# Tray2_ARM.net
KiCad netlist of a schematic drawn in Altium Designer
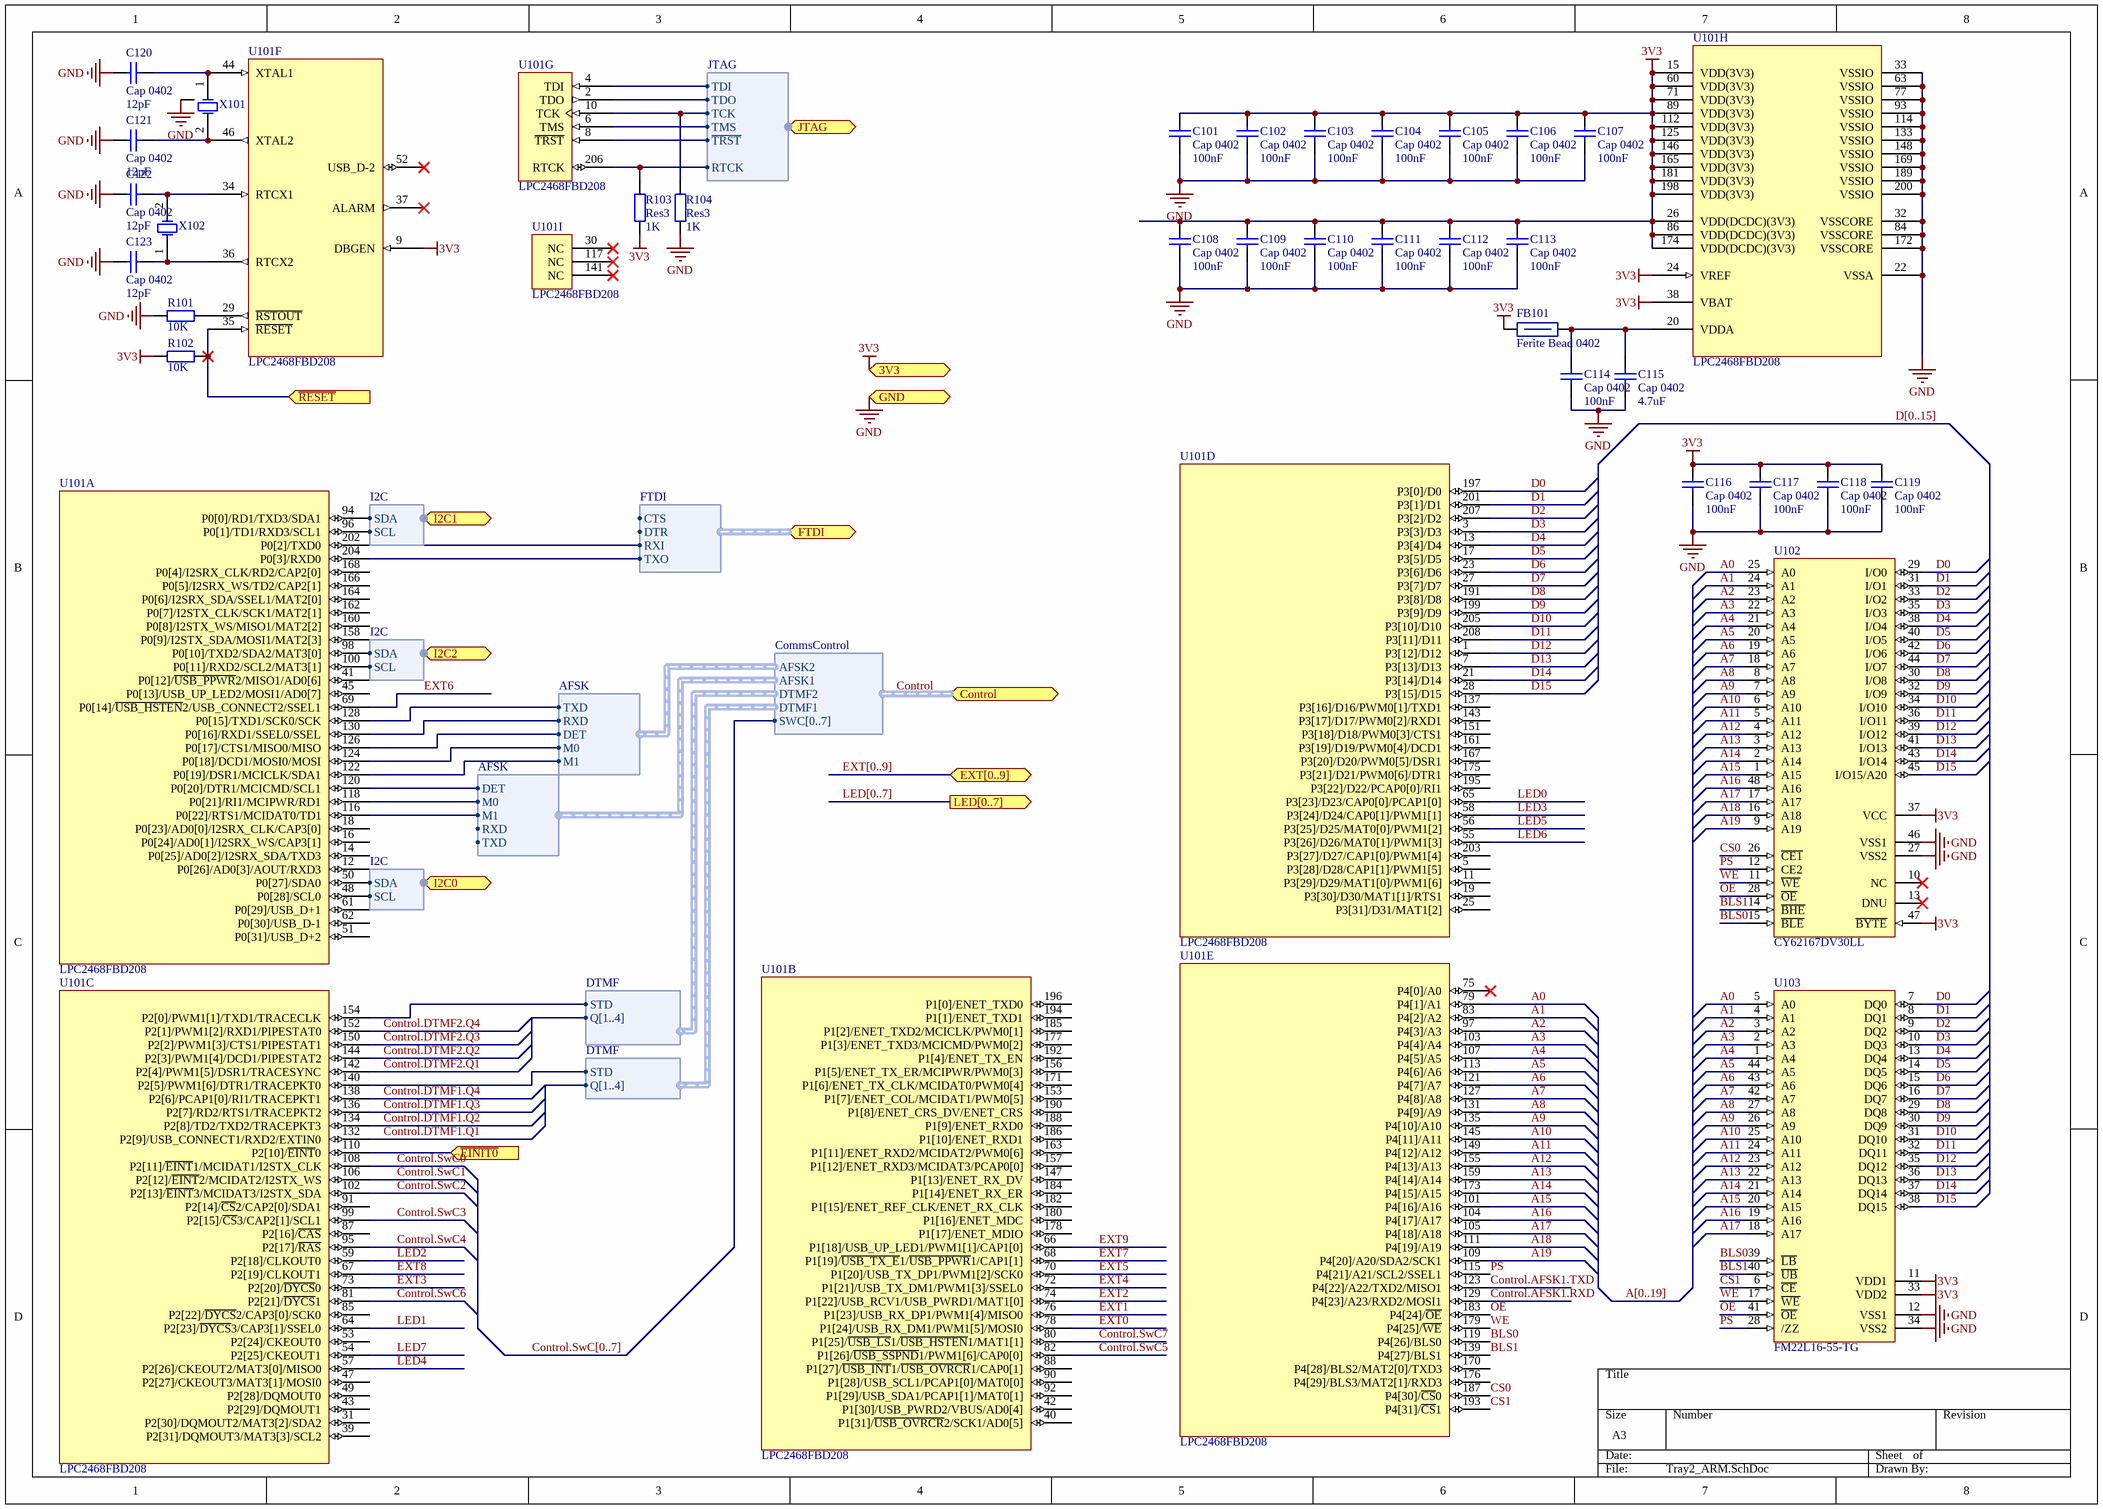
[diagram p0: Tray2_ARM.SchDoc]

(export (version "E")
  (design (tool "Eeschema 10.0.6"))
  (components
    (comp (ref "C101")
      (value "Cap 0402")
      (footprint "CAPC1005X06L")
      (description "Capacitor")
      (fields (field (name "ALTIUM_VALUE") "100nF") (field (name "PUBLISHER") "Altium Limited"))
      (libsource (lib "CSC") (part "Cap 0402"))
    )
    (comp (ref "C102")
      (value "Cap 0402")
      (footprint "CAPC1005X06L")
      (description "Capacitor")
      (fields (field (name "ALTIUM_VALUE") "100nF") (field (name "PUBLISHER") "Altium Limited"))
      (libsource (lib "CSC") (part "Cap 0402"))
    )
    (comp (ref "C103")
      (value "Cap 0402")
      (footprint "CAPC1005X06L")
      (description "Capacitor")
      (fields (field (name "ALTIUM_VALUE") "100nF") (field (name "PUBLISHER") "Altium Limited"))
      (libsource (lib "CSC") (part "Cap 0402"))
    )
    (comp (ref "C104")
      (value "Cap 0402")
      (footprint "CAPC1005X06L")
      (description "Capacitor")
      (fields (field (name "ALTIUM_VALUE") "100nF") (field (name "PUBLISHER") "Altium Limited"))
      (libsource (lib "CSC") (part "Cap 0402"))
    )
    (comp (ref "C105")
      (value "Cap 0402")
      (footprint "CAPC1005X06L")
      (description "Capacitor")
      (fields (field (name "ALTIUM_VALUE") "100nF") (field (name "PUBLISHER") "Altium Limited"))
      (libsource (lib "CSC") (part "Cap 0402"))
    )
    (comp (ref "C106")
      (value "Cap 0402")
      (footprint "CAPC1005X06L")
      (description "Capacitor")
      (fields (field (name "ALTIUM_VALUE") "100nF") (field (name "PUBLISHER") "Altium Limited"))
      (libsource (lib "CSC") (part "Cap 0402"))
    )
    (comp (ref "C107")
      (value "Cap 0402")
      (footprint "CAPC1005X06L")
      (description "Capacitor")
      (fields (field (name "ALTIUM_VALUE") "100nF") (field (name "PUBLISHER") "Altium Limited"))
      (libsource (lib "CSC") (part "Cap 0402"))
    )
    (comp (ref "C108")
      (value "Cap 0402")
      (footprint "CAPC1005X06L")
      (description "Capacitor")
      (fields (field (name "ALTIUM_VALUE") "100nF") (field (name "PUBLISHER") "Altium Limited"))
      (libsource (lib "CSC") (part "Cap 0402"))
    )
    (comp (ref "C109")
      (value "Cap 0402")
      (footprint "CAPC1005X06L")
      (description "Capacitor")
      (fields (field (name "ALTIUM_VALUE") "100nF") (field (name "PUBLISHER") "Altium Limited"))
      (libsource (lib "CSC") (part "Cap 0402"))
    )
    (comp (ref "C110")
      (value "Cap 0402")
      (footprint "CAPC1005X06L")
      (description "Capacitor")
      (fields (field (name "ALTIUM_VALUE") "100nF") (field (name "PUBLISHER") "Altium Limited"))
      (libsource (lib "CSC") (part "Cap 0402"))
    )
    (comp (ref "C111")
      (value "Cap 0402")
      (footprint "CAPC1005X06L")
      (description "Capacitor")
      (fields (field (name "ALTIUM_VALUE") "100nF") (field (name "PUBLISHER") "Altium Limited"))
      (libsource (lib "CSC") (part "Cap 0402"))
    )
    (comp (ref "C112")
      (value "Cap 0402")
      (footprint "CAPC1005X06L")
      (description "Capacitor")
      (fields (field (name "ALTIUM_VALUE") "100nF") (field (name "PUBLISHER") "Altium Limited"))
      (libsource (lib "CSC") (part "Cap 0402"))
    )
    (comp (ref "C113")
      (value "Cap 0402")
      (footprint "CAPC1005X06L")
      (description "Capacitor")
      (fields (field (name "ALTIUM_VALUE") "100nF") (field (name "PUBLISHER") "Altium Limited"))
      (libsource (lib "CSC") (part "Cap 0402"))
    )
    (comp (ref "C114")
      (value "Cap 0402")
      (footprint "CAPC1005X06L")
      (description "Capacitor")
      (fields (field (name "ALTIUM_VALUE") "100nF") (field (name "PUBLISHER") "Altium Limited"))
      (libsource (lib "CSC") (part "Cap 0402"))
    )
    (comp (ref "C115")
      (value "Cap 0402")
      (footprint "CAPC1005X06L")
      (description "Capacitor")
      (fields (field (name "ALTIUM_VALUE") "4.7uF") (field (name "PUBLISHER") "Altium Limited"))
      (libsource (lib "CSC") (part "Cap 0402"))
    )
    (comp (ref "C116")
      (value "Cap 0402")
      (footprint "CAPC1005X06L")
      (description "Capacitor")
      (fields (field (name "ALTIUM_VALUE") "100nF") (field (name "PUBLISHER") "Altium Limited"))
      (libsource (lib "CSC") (part "Cap 0402"))
    )
    (comp (ref "C117")
      (value "Cap 0402")
      (footprint "CAPC1005X06L")
      (description "Capacitor")
      (fields (field (name "ALTIUM_VALUE") "100nF") (field (name "PUBLISHER") "Altium Limited"))
      (libsource (lib "CSC") (part "Cap 0402"))
    )
    (comp (ref "C118")
      (value "Cap 0402")
      (footprint "CAPC1005X06L")
      (description "Capacitor")
      (fields (field (name "ALTIUM_VALUE") "100nF") (field (name "PUBLISHER") "Altium Limited"))
      (libsource (lib "CSC") (part "Cap 0402"))
    )
    (comp (ref "C119")
      (value "Cap 0402")
      (footprint "CAPC1005X06L")
      (description "Capacitor")
      (fields (field (name "ALTIUM_VALUE") "100nF") (field (name "PUBLISHER") "Altium Limited"))
      (libsource (lib "CSC") (part "Cap 0402"))
    )
    (comp (ref "C120")
      (value "Cap 0402")
      (footprint "CAPC1005X06L")
      (description "Capacitor")
      (fields (field (name "ALTIUM_VALUE") "12pF") (field (name "PUBLISHER") "Altium Limited"))
      (libsource (lib "CSC") (part "Cap 0402"))
    )
    (comp (ref "C121")
      (value "Cap 0402")
      (footprint "CAPC1005X06L")
      (description "Capacitor")
      (fields (field (name "ALTIUM_VALUE") "12pF") (field (name "PUBLISHER") "Altium Limited"))
      (libsource (lib "CSC") (part "Cap 0402"))
    )
    (comp (ref "C122")
      (value "Cap 0402")
      (footprint "CAPC1005X06L")
      (description "Capacitor")
      (fields (field (name "ALTIUM_VALUE") "12pF") (field (name "PUBLISHER") "Altium Limited"))
      (libsource (lib "CSC") (part "Cap 0402"))
    )
    (comp (ref "C123")
      (value "Cap 0402")
      (footprint "CAPC1005X06L")
      (description "Capacitor")
      (fields (field (name "ALTIUM_VALUE") "12pF") (field (name "PUBLISHER") "Altium Limited"))
      (libsource (lib "CSC") (part "Cap 0402"))
    )
    (comp (ref "FB101")
      (value "Ferite Bead 0402")
      (footprint "INDC1005X06L")
      (description "Ferite Bead : 0402")
      (fields (field (name "PUBLISHER") "Altium Limited"))
      (libsource (lib "CSC") (part "FB_0402"))
    )
    (comp (ref "R101")
      (value "10K")
      (footprint "RESC1005X06L")
      (description "Resistor")
      (fields (field (name "Comment") "Res3") (field (name "PUBLISHER") "Altium Limited"))
      (libsource (lib "CSC") (part "Res3"))
    )
    (comp (ref "R102")
      (value "10K")
      (footprint "RESC1005X06L")
      (description "Resistor")
      (fields (field (name "Comment") "Res3") (field (name "PUBLISHER") "Altium Limited"))
      (libsource (lib "CSC") (part "Res3"))
    )
    (comp (ref "R103")
      (value "Res3")
      (footprint "RESC1005X06L")
      (description "Resistor")
      (fields (field (name "ALTIUM_VALUE") "1K") (field (name "PUBLISHER") "Altium Limited"))
      (libsource (lib "") (part "Res3_1"))
    )
    (comp (ref "R104")
      (value "Res3")
      (footprint "RESC1005X06L")
      (description "Resistor")
      (fields (field (name "ALTIUM_VALUE") "1K") (field (name "PUBLISHER") "Altium Limited"))
      (libsource (lib "") (part "Res3_1"))
    )
    (comp (ref "U101")
      (value "LPC2468FBD208")
      (footprint "TSQFP50P3000X3000X160-208L")
      (description "ARM7 16/32-Bit Microcontroller, 512KB Flash, 98KB RAM, 208-Lead LQFP")
      (fields (field (name "PUBLISHER") "Altium Limited"))
      (libsource (lib "CSC") (part "LPC2468FBD208"))
    )
    (comp (ref "U102")
      (value "CY62167DV30LL")
      (footprint "TSSOP50P2000X120-48L")
      (description "16-Mbit (1M x 16) Static RAM")
      (fields (field (name "PUBLISHER") "Altium Limited"))
      (libsource (lib "CSC") (part "CY62167DV30LL"))
    )
    (comp (ref "U103")
      (value "FM22L16-55-TG")
      (footprint "TSOP80P1180X120-44L")
      (description "FRAM, 2MB, 3V, 60NS, 44TSOP2")
      (libsource (lib "CSC") (part "FM22L16-55-TG"))
    )
    (comp (ref "X101")
      (value "Crystal Oscilator")
      (footprint "7M")
      (description "Crystal Oscillator")
      (fields (field (name "PUBLISHER") "Altium Limited"))
      (libsource (lib "CSC") (part "C.O. 4pins"))
    )
    (comp (ref "X102")
      (value "Crystal Oscilator")
      (footprint "9H T10")
      (description "Crystal Oscillator")
      (fields (field (name "PUBLISHER") "Altium Limited"))
      (libsource (lib "CSC") (part "C.O. 2pins"))
    )
  )
  (nets
    (net (code "7") (name "/A0") (class "Default")
      (node (ref "U101") (pin "79") (pinfunction "P4[1]/A1_79") (pintype "bidirectional"))
      (node (ref "U102") (pin "25") (pinfunction "A0_25") (pintype "input"))
      (node (ref "U103") (pin "5") (pinfunction "A0_5") (pintype "input"))
    )
    (net (code "8") (name "/A1") (class "Default")
      (node (ref "U101") (pin "83") (pinfunction "P4[2]/A2_83") (pintype "bidirectional"))
      (node (ref "U102") (pin "24") (pinfunction "A1_24") (pintype "input"))
      (node (ref "U103") (pin "4") (pinfunction "A1_4") (pintype "input"))
    )
    (net (code "9") (name "/A2") (class "Default")
      (node (ref "U101") (pin "97") (pinfunction "P4[3]/A3_97") (pintype "bidirectional"))
      (node (ref "U102") (pin "23") (pinfunction "A2_23") (pintype "input"))
      (node (ref "U103") (pin "3") (pinfunction "A2_3") (pintype "input"))
    )
    (net (code "10") (name "/A3") (class "Default")
      (node (ref "U101") (pin "103") (pinfunction "P4[4]/A4_103") (pintype "bidirectional"))
      (node (ref "U102") (pin "22") (pinfunction "A3_22") (pintype "input"))
      (node (ref "U103") (pin "2") (pinfunction "A3_2") (pintype "input"))
    )
    (net (code "11") (name "/A4") (class "Default")
      (node (ref "U101") (pin "107") (pinfunction "P4[5]/A5_107") (pintype "bidirectional"))
      (node (ref "U102") (pin "21") (pinfunction "A4_21") (pintype "input"))
      (node (ref "U103") (pin "1") (pinfunction "A4_1") (pintype "input"))
    )
    (net (code "12") (name "/A5") (class "Default")
      (node (ref "U101") (pin "113") (pinfunction "P4[6]/A6_113") (pintype "bidirectional"))
      (node (ref "U102") (pin "20") (pinfunction "A5_20") (pintype "input"))
      (node (ref "U103") (pin "44") (pinfunction "A5_44") (pintype "input"))
    )
    (net (code "13") (name "/A6") (class "Default")
      (node (ref "U101") (pin "121") (pinfunction "P4[7]/A7_121") (pintype "bidirectional"))
      (node (ref "U102") (pin "19") (pinfunction "A6_19") (pintype "input"))
      (node (ref "U103") (pin "43") (pinfunction "A6_43") (pintype "input"))
    )
    (net (code "14") (name "/A7") (class "Default")
      (node (ref "U101") (pin "127") (pinfunction "P4[8]/A8_127") (pintype "bidirectional"))
      (node (ref "U102") (pin "18") (pinfunction "A7_18") (pintype "input"))
      (node (ref "U103") (pin "42") (pinfunction "A7_42") (pintype "input"))
    )
    (net (code "15") (name "/A8") (class "Default")
      (node (ref "U101") (pin "131") (pinfunction "P4[9]/A9_131") (pintype "bidirectional"))
      (node (ref "U102") (pin "8") (pinfunction "A8_8") (pintype "input"))
      (node (ref "U103") (pin "27") (pinfunction "A8_27") (pintype "input"))
    )
    (net (code "16") (name "/A9") (class "Default")
      (node (ref "U101") (pin "135") (pinfunction "P4[10]/A10_135") (pintype "bidirectional"))
      (node (ref "U102") (pin "7") (pinfunction "A9_7") (pintype "input"))
      (node (ref "U103") (pin "26") (pinfunction "A9_26") (pintype "input"))
    )
    (net (code "17") (name "/A10") (class "Default")
      (node (ref "U101") (pin "145") (pinfunction "P4[11]/A11_145") (pintype "bidirectional"))
      (node (ref "U102") (pin "6") (pinfunction "A10_6") (pintype "input"))
      (node (ref "U103") (pin "25") (pinfunction "A10_25") (pintype "input"))
    )
    (net (code "18") (name "/A11") (class "Default")
      (node (ref "U101") (pin "149") (pinfunction "P4[12]/A12_149") (pintype "bidirectional"))
      (node (ref "U102") (pin "5") (pinfunction "A11_5") (pintype "input"))
      (node (ref "U103") (pin "24") (pinfunction "A11_24") (pintype "input"))
    )
    (net (code "19") (name "/A12") (class "Default")
      (node (ref "U101") (pin "155") (pinfunction "P4[13]/A13_155") (pintype "bidirectional"))
      (node (ref "U102") (pin "4") (pinfunction "A12_4") (pintype "input"))
      (node (ref "U103") (pin "23") (pinfunction "A12_23") (pintype "input"))
    )
    (net (code "20") (name "/A13") (class "Default")
      (node (ref "U101") (pin "159") (pinfunction "P4[14]/A14_159") (pintype "bidirectional"))
      (node (ref "U102") (pin "3") (pinfunction "A13_3") (pintype "input"))
      (node (ref "U103") (pin "22") (pinfunction "A13_22") (pintype "input"))
    )
    (net (code "21") (name "/A14") (class "Default")
      (node (ref "U101") (pin "173") (pinfunction "P4[15]/A15_173") (pintype "bidirectional"))
      (node (ref "U102") (pin "2") (pinfunction "A14_2") (pintype "input"))
      (node (ref "U103") (pin "21") (pinfunction "A14_21") (pintype "input"))
    )
    (net (code "22") (name "/A15") (class "Default")
      (node (ref "U101") (pin "101") (pinfunction "P4[16]/A16_101") (pintype "bidirectional"))
      (node (ref "U102") (pin "1") (pinfunction "A15_1") (pintype "input"))
      (node (ref "U103") (pin "20") (pinfunction "A15_20") (pintype "input"))
    )
    (net (code "23") (name "/A16") (class "Default")
      (node (ref "U101") (pin "104") (pinfunction "P4[17]/A17_104") (pintype "bidirectional"))
      (node (ref "U102") (pin "48") (pinfunction "A16_48") (pintype "input"))
      (node (ref "U103") (pin "19") (pinfunction "A16_19") (pintype "input"))
    )
    (net (code "24") (name "/A17") (class "Default")
      (node (ref "U101") (pin "105") (pinfunction "P4[18]/A18_105") (pintype "bidirectional"))
      (node (ref "U102") (pin "17") (pinfunction "A17_17") (pintype "input"))
      (node (ref "U103") (pin "18") (pinfunction "A17_18") (pintype "input"))
    )
    (net (code "25") (name "/A18") (class "Default")
      (node (ref "U101") (pin "111") (pinfunction "P4[19]/A19_111") (pintype "bidirectional"))
      (node (ref "U102") (pin "16") (pinfunction "A18_16") (pintype "input"))
    )
    (net (code "26") (name "/A19") (class "Default")
      (node (ref "U101") (pin "109") (pinfunction "P4[20]/A20/SDA2/SCK1_109") (pintype "bidirectional"))
      (node (ref "U102") (pin "9") (pinfunction "A19_9") (pintype "input"))
    )
    (net (code "28") (name "/BLS0") (class "Default")
      (node (ref "U101") (pin "119") (pinfunction "P4[26]/BLS0_119") (pintype "bidirectional"))
      (node (ref "U102") (pin "15") (pinfunction "~{BLE}_15") (pintype "input"))
      (node (ref "U103") (pin "39") (pinfunction "~{LB}_39") (pintype "input"))
    )
    (net (code "29") (name "/BLS1") (class "Default")
      (node (ref "U101") (pin "139") (pinfunction "P4[27]/BLS1_139") (pintype "bidirectional"))
      (node (ref "U102") (pin "14") (pinfunction "~{BHE}_14") (pintype "input"))
      (node (ref "U103") (pin "40") (pinfunction "~{UB}_40") (pintype "input"))
    )
    (net (code "30") (name "/CS0") (class "Default")
      (node (ref "U101") (pin "187") (pinfunction "P4[30]/~{CS}0_187") (pintype "bidirectional"))
      (node (ref "U102") (pin "26") (pinfunction "~{CE1}_26") (pintype "input"))
    )
    (net (code "31") (name "/CS1") (class "Default")
      (node (ref "U101") (pin "193") (pinfunction "P4[31]/~{CS}1_193") (pintype "bidirectional"))
      (node (ref "U103") (pin "6") (pinfunction "~{CE}_6") (pintype "input"))
    )
    (net (code "32") (name "/Control.AFSK1.RXD") (class "Default")
      (node (ref "U101") (pin "129") (pinfunction "P4[23]/A23/RXD2/MOSI1_129") (pintype "bidirectional"))
    )
    (net (code "33") (name "/Control.AFSK1.TXD") (class "Default")
      (node (ref "U101") (pin "123") (pinfunction "P4[22]/A22/TXD2/MISO1_123") (pintype "bidirectional"))
    )
    (net (code "34") (name "/Control.DTMF1.Q1") (class "Default")
      (node (ref "U101") (pin "132") (pinfunction "P2[9]/USB_CONNECT1/RXD2/EXTIN0_132") (pintype "bidirectional"))
    )
    (net (code "35") (name "/Control.DTMF1.Q2") (class "Default")
      (node (ref "U101") (pin "134") (pinfunction "P2[8]/TD2/TXD2/TRACEPKT3_134") (pintype "bidirectional"))
    )
    (net (code "36") (name "/Control.DTMF1.Q3") (class "Default")
      (node (ref "U101") (pin "136") (pinfunction "P2[7]/RD2/RTS1/TRACEPKT2_136") (pintype "bidirectional"))
    )
    (net (code "37") (name "/Control.DTMF1.Q4") (class "Default")
      (node (ref "U101") (pin "138") (pinfunction "P2[6]/PCAP1[0]/RI1/TRACEPKT1_138") (pintype "bidirectional"))
    )
    (net (code "38") (name "/Control.DTMF2.Q1") (class "Default")
      (node (ref "U101") (pin "142") (pinfunction "P2[4]/PWM1[5]/DSR1/TRACESYNC_142") (pintype "bidirectional"))
    )
    (net (code "39") (name "/Control.DTMF2.Q2") (class "Default")
      (node (ref "U101") (pin "144") (pinfunction "P2[3]/PWM1[4]/DCD1/PIPESTAT2_144") (pintype "bidirectional"))
    )
    (net (code "40") (name "/Control.DTMF2.Q3") (class "Default")
      (node (ref "U101") (pin "150") (pinfunction "P2[2]/PWM1[3]/CTS1/PIPESTAT1_150") (pintype "bidirectional"))
    )
    (net (code "41") (name "/Control.DTMF2.Q4") (class "Default")
      (node (ref "U101") (pin "152") (pinfunction "P2[1]/PWM1[2]/RXD1/PIPESTAT0_152") (pintype "bidirectional"))
    )
    (net (code "42") (name "/Control.SwC0") (class "Default")
      (node (ref "U101") (pin "108") (pinfunction "P2[11]/~{EINT}1/MCIDAT1/I2STX_CLK_108") (pintype "bidirectional"))
    )
    (net (code "43") (name "/Control.SwC1") (class "Default")
      (node (ref "U101") (pin "106") (pinfunction "P2[12]/~{EINT}2/MCIDAT2/I2STX_WS_106") (pintype "bidirectional"))
    )
    (net (code "44") (name "/Control.SwC2") (class "Default")
      (node (ref "U101") (pin "102") (pinfunction "P2[13]/~{EINT}3/MCIDAT3/I2STX_SDA_102") (pintype "bidirectional"))
    )
    (net (code "45") (name "/Control.SwC3") (class "Default")
      (node (ref "U101") (pin "99") (pinfunction "P2[15]/~{CS}3/CAP2[1]/SCL1_99") (pintype "bidirectional"))
    )
    (net (code "46") (name "/Control.SwC4") (class "Default")
      (node (ref "U101") (pin "95") (pinfunction "P2[17]/~{RAS}_95") (pintype "bidirectional"))
    )
    (net (code "47") (name "/Control.SwC5") (class "Default")
      (node (ref "U101") (pin "82") (pinfunction "P1[26]/~{USB_SSPND}1/PWM1[6]/CAP0[0]_82") (pintype "bidirectional"))
    )
    (net (code "48") (name "/Control.SwC6") (class "Default")
      (node (ref "U101") (pin "81") (pinfunction "P2[21]/~{DYCS}1_81") (pintype "bidirectional"))
    )
    (net (code "49") (name "/Control.SwC7") (class "Default")
      (node (ref "U101") (pin "80") (pinfunction "P1[25]/~{USB_LS}1/~{USB_HSTEN}1/MAT1[1]_80") (pintype "bidirectional"))
    )
    (net (code "50") (name "/D0") (class "Default")
      (node (ref "U101") (pin "197") (pinfunction "P3[0]/D0_197") (pintype "bidirectional"))
      (node (ref "U102") (pin "29") (pinfunction "I/O0_29") (pintype "bidirectional"))
      (node (ref "U103") (pin "7") (pinfunction "DQ0_7") (pintype "bidirectional"))
    )
    (net (code "51") (name "/D1") (class "Default")
      (node (ref "U101") (pin "201") (pinfunction "P3[1]/D1_201") (pintype "bidirectional"))
      (node (ref "U102") (pin "31") (pinfunction "I/O1_31") (pintype "bidirectional"))
      (node (ref "U103") (pin "8") (pinfunction "DQ1_8") (pintype "bidirectional"))
    )
    (net (code "52") (name "/D2") (class "Default")
      (node (ref "U101") (pin "207") (pinfunction "P3[2]/D2_207") (pintype "bidirectional"))
      (node (ref "U102") (pin "33") (pinfunction "I/O2_33") (pintype "bidirectional"))
      (node (ref "U103") (pin "9") (pinfunction "DQ2_9") (pintype "bidirectional"))
    )
    (net (code "53") (name "/D3") (class "Default")
      (node (ref "U101") (pin "3") (pinfunction "P3[3]/D3_3") (pintype "bidirectional"))
      (node (ref "U102") (pin "35") (pinfunction "I/O3_35") (pintype "bidirectional"))
      (node (ref "U103") (pin "10") (pinfunction "DQ3_10") (pintype "bidirectional"))
    )
    (net (code "54") (name "/D4") (class "Default")
      (node (ref "U101") (pin "13") (pinfunction "P3[4]/D4_13") (pintype "bidirectional"))
      (node (ref "U102") (pin "38") (pinfunction "I/O4_38") (pintype "bidirectional"))
      (node (ref "U103") (pin "13") (pinfunction "DQ4_13") (pintype "bidirectional"))
    )
    (net (code "55") (name "/D5") (class "Default")
      (node (ref "U101") (pin "17") (pinfunction "P3[5]/D5_17") (pintype "bidirectional"))
      (node (ref "U102") (pin "40") (pinfunction "I/O5_40") (pintype "bidirectional"))
      (node (ref "U103") (pin "14") (pinfunction "DQ5_14") (pintype "bidirectional"))
    )
    (net (code "56") (name "/D6") (class "Default")
      (node (ref "U101") (pin "23") (pinfunction "P3[6]/D6_23") (pintype "bidirectional"))
      (node (ref "U102") (pin "42") (pinfunction "I/O6_42") (pintype "bidirectional"))
      (node (ref "U103") (pin "15") (pinfunction "DQ6_15") (pintype "bidirectional"))
    )
    (net (code "57") (name "/D7") (class "Default")
      (node (ref "U101") (pin "27") (pinfunction "P3[7]/D7_27") (pintype "bidirectional"))
      (node (ref "U102") (pin "44") (pinfunction "I/O7_44") (pintype "bidirectional"))
      (node (ref "U103") (pin "16") (pinfunction "DQ7_16") (pintype "bidirectional"))
    )
    (net (code "58") (name "/D8") (class "Default")
      (node (ref "U101") (pin "191") (pinfunction "P3[8]/D8_191") (pintype "bidirectional"))
      (node (ref "U102") (pin "30") (pinfunction "I/O8_30") (pintype "bidirectional"))
      (node (ref "U103") (pin "29") (pinfunction "DQ8_29") (pintype "bidirectional"))
    )
    (net (code "59") (name "/D9") (class "Default")
      (node (ref "U101") (pin "199") (pinfunction "P3[9]/D9_199") (pintype "bidirectional"))
      (node (ref "U102") (pin "32") (pinfunction "I/O9_32") (pintype "bidirectional"))
      (node (ref "U103") (pin "30") (pinfunction "DQ9_30") (pintype "bidirectional"))
    )
    (net (code "60") (name "/D10") (class "Default")
      (node (ref "U101") (pin "205") (pinfunction "P3[10]/D10_205") (pintype "bidirectional"))
      (node (ref "U102") (pin "34") (pinfunction "I/O10_34") (pintype "bidirectional"))
      (node (ref "U103") (pin "31") (pinfunction "DQ10_31") (pintype "bidirectional"))
    )
    (net (code "61") (name "/D11") (class "Default")
      (node (ref "U101") (pin "208") (pinfunction "P3[11]/D11_208") (pintype "bidirectional"))
      (node (ref "U102") (pin "36") (pinfunction "I/O11_36") (pintype "bidirectional"))
      (node (ref "U103") (pin "32") (pinfunction "DQ11_32") (pintype "bidirectional"))
    )
    (net (code "62") (name "/D12") (class "Default")
      (node (ref "U101") (pin "1") (pinfunction "P3[12]/D12_1") (pintype "bidirectional"))
      (node (ref "U102") (pin "39") (pinfunction "I/O12_39") (pintype "bidirectional"))
      (node (ref "U103") (pin "35") (pinfunction "DQ12_35") (pintype "bidirectional"))
    )
    (net (code "63") (name "/D13") (class "Default")
      (node (ref "U101") (pin "7") (pinfunction "P3[13]/D13_7") (pintype "bidirectional"))
      (node (ref "U102") (pin "41") (pinfunction "I/O13_41") (pintype "bidirectional"))
      (node (ref "U103") (pin "36") (pinfunction "DQ13_36") (pintype "bidirectional"))
    )
    (net (code "64") (name "/D14") (class "Default")
      (node (ref "U101") (pin "21") (pinfunction "P3[14]/D14_21") (pintype "bidirectional"))
      (node (ref "U102") (pin "43") (pinfunction "I/O14_43") (pintype "bidirectional"))
      (node (ref "U103") (pin "37") (pinfunction "DQ14_37") (pintype "bidirectional"))
    )
    (net (code "65") (name "/D15") (class "Default")
      (node (ref "U101") (pin "28") (pinfunction "P3[15]/D15_28") (pintype "bidirectional"))
      (node (ref "U102") (pin "45") (pinfunction "I/O15/A20_45") (pintype "bidirectional"))
      (node (ref "U103") (pin "38") (pinfunction "DQ15_38") (pintype "bidirectional"))
    )
    (net (code "68") (name "/EXT0") (class "Default")
      (node (ref "U101") (pin "78") (pinfunction "P1[24]/USB_RX_DM1/PWM1[5]/MOSI0_78") (pintype "bidirectional"))
    )
    (net (code "69") (name "/EXT1") (class "Default")
      (node (ref "U101") (pin "76") (pinfunction "P1[23]/USB_RX_DP1/PWM1[4]/MISO0_76") (pintype "bidirectional"))
    )
    (net (code "70") (name "/EXT2") (class "Default")
      (node (ref "U101") (pin "74") (pinfunction "P1[22]/USB_RCV1/USB_PWRD1/MAT1[0]_74") (pintype "bidirectional"))
    )
    (net (code "71") (name "/EXT3") (class "Default")
      (node (ref "U101") (pin "73") (pinfunction "P2[20]/~{DYCS}0_73") (pintype "bidirectional"))
    )
    (net (code "72") (name "/EXT4") (class "Default")
      (node (ref "U101") (pin "72") (pinfunction "P1[21]/USB_TX_DM1/PWM1[3]/SSEL0_72") (pintype "bidirectional"))
    )
    (net (code "73") (name "/EXT5") (class "Default")
      (node (ref "U101") (pin "70") (pinfunction "P1[20]/USB_TX_DP1/PWM1[2]/SCK0_70") (pintype "bidirectional"))
    )
    (net (code "74") (name "/EXT6") (class "Default")
      (node (ref "U101") (pin "69") (pinfunction "P0[14]/~{USB_HSTEN}2/USB_CONNECT2/SSEL1_69") (pintype "bidirectional"))
    )
    (net (code "75") (name "/EXT7") (class "Default")
      (node (ref "U101") (pin "68") (pinfunction "P1[19]/~{USB_TX_E}1/~{USB_PPWR}1/CAP1[1]_68") (pintype "bidirectional"))
    )
    (net (code "76") (name "/EXT8") (class "Default")
      (node (ref "U101") (pin "67") (pinfunction "P2[19]/CLKOUT1_67") (pintype "bidirectional"))
    )
    (net (code "77") (name "/EXT9") (class "Default")
      (node (ref "U101") (pin "66") (pinfunction "P1[18]/USB_UP_LED1/PWM1[1]/CAP1[0]_66") (pintype "bidirectional"))
    )
    (net (code "79") (name "/LED0") (class "Default")
      (node (ref "U101") (pin "65") (pinfunction "P3[23]/D23/CAP0[0]/PCAP1[0]_65") (pintype "bidirectional"))
    )
    (net (code "80") (name "/LED1") (class "Default")
      (node (ref "U101") (pin "64") (pinfunction "P2[23]/~{DYCS}3/CAP3[1]/SSEL0_64") (pintype "bidirectional"))
    )
    (net (code "81") (name "/LED2") (class "Default")
      (node (ref "U101") (pin "59") (pinfunction "P2[18]/CLKOUT0_59") (pintype "bidirectional"))
    )
    (net (code "82") (name "/LED3") (class "Default")
      (node (ref "U101") (pin "58") (pinfunction "P3[24]/D24/CAP0[1]/PWM1[1]_58") (pintype "bidirectional"))
    )
    (net (code "83") (name "/LED4") (class "Default")
      (node (ref "U101") (pin "57") (pinfunction "P2[26]/CKEOUT2/MAT3[0]/MISO0_57") (pintype "bidirectional"))
    )
    (net (code "84") (name "/LED5") (class "Default")
      (node (ref "U101") (pin "56") (pinfunction "P3[25]/D25/MAT0[0]/PWM1[2]_56") (pintype "bidirectional"))
    )
    (net (code "85") (name "/LED6") (class "Default")
      (node (ref "U101") (pin "55") (pinfunction "P3[26]/D26/MAT0[1]/PWM1[3]_55") (pintype "bidirectional"))
    )
    (net (code "86") (name "/LED7") (class "Default")
      (node (ref "U101") (pin "54") (pinfunction "P2[25]/CKEOUT1_54") (pintype "bidirectional"))
    )
    (net (code "88") (name "/OE") (class "Default")
      (node (ref "U101") (pin "183") (pinfunction "P4[24]/~{OE}_183") (pintype "bidirectional"))
      (node (ref "U102") (pin "28") (pinfunction "~{OE}_28") (pintype "input"))
      (node (ref "U103") (pin "41") (pinfunction "~{OE}_41") (pintype "input"))
    )
    (net (code "89") (name "/PS") (class "Default")
      (node (ref "U101") (pin "115") (pinfunction "P4[21]/A21/SCL2/SSEL1_115") (pintype "bidirectional"))
      (node (ref "U102") (pin "12") (pinfunction "CE2_12") (pintype "input"))
      (node (ref "U103") (pin "28") (pinfunction "/ZZ_28") (pintype "input"))
    )
    (net (code "90") (name "/RTCK") (class "Default")
      (node (ref "R103") (pin "1") (pinfunction "1_1") (pintype "passive"))
      (node (ref "U101") (pin "206") (pinfunction "RTCK_206") (pintype "bidirectional"))
    )
    (net (code "91") (name "/RXI") (class "Default")
      (node (ref "U101") (pin "202") (pinfunction "P0[2]/TXD0_202") (pintype "bidirectional"))
    )
    (net (code "92") (name "/TCK") (class "Default")
      (node (ref "R104") (pin "1") (pinfunction "1_1") (pintype "passive"))
      (node (ref "U101") (pin "10") (pinfunction "TCK_10") (pintype "input"))
    )
    (net (code "93") (name "/TDI") (class "Default")
      (node (ref "U101") (pin "4") (pinfunction "TDI_4") (pintype "input"))
    )
    (net (code "94") (name "/TDO") (class "Default")
      (node (ref "U101") (pin "2") (pinfunction "TDO_2") (pintype "output"))
    )
    (net (code "95") (name "/TMS") (class "Default")
      (node (ref "U101") (pin "6") (pinfunction "TMS_6") (pintype "input"))
    )
    (net (code "96") (name "/TXO") (class "Default")
      (node (ref "U101") (pin "204") (pinfunction "P0[3]/RXD0_204") (pintype "bidirectional"))
    )
    (net (code "97") (name "/WE") (class "Default")
      (node (ref "U101") (pin "179") (pinfunction "P4[25]/~{WE}_179") (pintype "bidirectional"))
      (node (ref "U102") (pin "11") (pinfunction "~{WE}_11") (pintype "input"))
      (node (ref "U103") (pin "17") (pinfunction "~{WE}_17") (pintype "input"))
    )
    (net (code "104") (name "/~{EINIT0}") (class "Default")
      (node (ref "U101") (pin "110") (pinfunction "P2[10]/~{EINT}0_110") (pintype "bidirectional"))
    )
    (net (code "105") (name "/~{RESET}") (class "Default")
      (node (ref "R102") (pin "1") (pinfunction "1_1") (pintype "passive"))
      (node (ref "U101") (pin "35") (pinfunction "~{RESET}_35") (pintype "input"))
    )
    (net (code "106") (name "/~{TRST}") (class "Default")
      (node (ref "U101") (pin "8") (pinfunction "~{TRST}_8") (pintype "input"))
    )
    (net (code "107") (name "3V3") (class "Default")
      (node (ref "C101") (pin "2") (pinfunction "2_2") (pintype "passive"))
      (node (ref "C102") (pin "2") (pinfunction "2_2") (pintype "passive"))
      (node (ref "C103") (pin "2") (pinfunction "2_2") (pintype "passive"))
      (node (ref "C104") (pin "2") (pinfunction "2_2") (pintype "passive"))
      (node (ref "C105") (pin "2") (pinfunction "2_2") (pintype "passive"))
      (node (ref "C106") (pin "2") (pinfunction "2_2") (pintype "passive"))
      (node (ref "C107") (pin "2") (pinfunction "2_2") (pintype "passive"))
      (node (ref "C108") (pin "2") (pinfunction "2_2") (pintype "passive"))
      (node (ref "C109") (pin "2") (pinfunction "2_2") (pintype "passive"))
      (node (ref "C110") (pin "2") (pinfunction "2_2") (pintype "passive"))
      (node (ref "C111") (pin "2") (pinfunction "2_2") (pintype "passive"))
      (node (ref "C112") (pin "2") (pinfunction "2_2") (pintype "passive"))
      (node (ref "C113") (pin "2") (pinfunction "2_2") (pintype "passive"))
      (node (ref "C116") (pin "2") (pinfunction "2_2") (pintype "passive"))
      (node (ref "C117") (pin "2") (pinfunction "2_2") (pintype "passive"))
      (node (ref "C118") (pin "2") (pinfunction "2_2") (pintype "passive"))
      (node (ref "C119") (pin "2") (pinfunction "2_2") (pintype "passive"))
      (node (ref "FB101") (pin "1") (pinfunction "1_1") (pintype "passive"))
      (node (ref "R102") (pin "2") (pinfunction "2_2") (pintype "passive"))
      (node (ref "R103") (pin "2") (pinfunction "2_2") (pintype "passive"))
      (node (ref "U101") (pin "112") (pinfunction "VDD(3V3)_112") (pintype "power_in"))
      (node (ref "U101") (pin "125") (pinfunction "VDD(3V3)_125") (pintype "power_in"))
      (node (ref "U101") (pin "146") (pinfunction "VDD(3V3)_146") (pintype "power_in"))
      (node (ref "U101") (pin "15") (pinfunction "VDD(3V3)_15") (pintype "power_in"))
      (node (ref "U101") (pin "165") (pinfunction "VDD(3V3)_165") (pintype "power_in"))
      (node (ref "U101") (pin "174") (pinfunction "VDD(DCDC)(3V3)_174") (pintype "power_in"))
      (node (ref "U101") (pin "181") (pinfunction "VDD(3V3)_181") (pintype "power_in"))
      (node (ref "U101") (pin "198") (pinfunction "VDD(3V3)_198") (pintype "power_in"))
      (node (ref "U101") (pin "24") (pinfunction "VREF_24") (pintype "input"))
      (node (ref "U101") (pin "26") (pinfunction "VDD(DCDC)(3V3)_26") (pintype "power_in"))
      (node (ref "U101") (pin "38") (pinfunction "VBAT_38") (pintype "power_in"))
      (node (ref "U101") (pin "60") (pinfunction "VDD(3V3)_60") (pintype "power_in"))
      (node (ref "U101") (pin "71") (pinfunction "VDD(3V3)_71") (pintype "power_in"))
      (node (ref "U101") (pin "86") (pinfunction "VDD(DCDC)(3V3)_86") (pintype "power_in"))
      (node (ref "U101") (pin "89") (pinfunction "VDD(3V3)_89") (pintype "power_in"))
      (node (ref "U101") (pin "9") (pinfunction "DBGEN_9") (pintype "input"))
      (node (ref "U102") (pin "37") (pinfunction "VCC_37") (pintype "power_in"))
      (node (ref "U102") (pin "47") (pinfunction "~{BYTE}_47") (pintype "input"))
      (node (ref "U103") (pin "11") (pinfunction "VDD1_11") (pintype "power_in"))
      (node (ref "U103") (pin "33") (pinfunction "VDD2_33") (pintype "power_in"))
    )
    (net (code "108") (name "GND") (class "Default")
      (node (ref "C101") (pin "1") (pinfunction "1_1") (pintype "passive"))
      (node (ref "C102") (pin "1") (pinfunction "1_1") (pintype "passive"))
      (node (ref "C103") (pin "1") (pinfunction "1_1") (pintype "passive"))
      (node (ref "C104") (pin "1") (pinfunction "1_1") (pintype "passive"))
      (node (ref "C105") (pin "1") (pinfunction "1_1") (pintype "passive"))
      (node (ref "C106") (pin "1") (pinfunction "1_1") (pintype "passive"))
      (node (ref "C107") (pin "1") (pinfunction "1_1") (pintype "passive"))
      (node (ref "C108") (pin "1") (pinfunction "1_1") (pintype "passive"))
      (node (ref "C109") (pin "1") (pinfunction "1_1") (pintype "passive"))
      (node (ref "C110") (pin "1") (pinfunction "1_1") (pintype "passive"))
      (node (ref "C111") (pin "1") (pinfunction "1_1") (pintype "passive"))
      (node (ref "C112") (pin "1") (pinfunction "1_1") (pintype "passive"))
      (node (ref "C113") (pin "1") (pinfunction "1_1") (pintype "passive"))
      (node (ref "C114") (pin "1") (pinfunction "1_1") (pintype "passive"))
      (node (ref "C115") (pin "1") (pinfunction "1_1") (pintype "passive"))
      (node (ref "C116") (pin "1") (pinfunction "1_1") (pintype "passive"))
      (node (ref "C117") (pin "1") (pinfunction "1_1") (pintype "passive"))
      (node (ref "C118") (pin "1") (pinfunction "1_1") (pintype "passive"))
      (node (ref "C119") (pin "1") (pinfunction "1_1") (pintype "passive"))
      (node (ref "C120") (pin "2") (pinfunction "2_2") (pintype "passive"))
      (node (ref "C121") (pin "1") (pinfunction "1_1") (pintype "passive"))
      (node (ref "C122") (pin "2") (pinfunction "2_2") (pintype "passive"))
      (node (ref "C123") (pin "1") (pinfunction "1_1") (pintype "passive"))
      (node (ref "R101") (pin "2") (pinfunction "2_2") (pintype "passive"))
      (node (ref "R104") (pin "2") (pinfunction "2_2") (pintype "passive"))
      (node (ref "U101") (pin "114") (pinfunction "VSSIO_114") (pintype "power_in"))
      (node (ref "U101") (pin "133") (pinfunction "VSSIO_133") (pintype "power_in"))
      (node (ref "U101") (pin "148") (pinfunction "VSSIO_148") (pintype "power_in"))
      (node (ref "U101") (pin "169") (pinfunction "VSSIO_169") (pintype "power_in"))
      (node (ref "U101") (pin "172") (pinfunction "VSSCORE_172") (pintype "power_in"))
      (node (ref "U101") (pin "189") (pinfunction "VSSIO_189") (pintype "power_in"))
      (node (ref "U101") (pin "200") (pinfunction "VSSIO_200") (pintype "power_in"))
      (node (ref "U101") (pin "22") (pinfunction "VSSA_22") (pintype "power_in"))
      (node (ref "U101") (pin "32") (pinfunction "VSSCORE_32") (pintype "power_in"))
      (node (ref "U101") (pin "33") (pinfunction "VSSIO_33") (pintype "power_in"))
      (node (ref "U101") (pin "63") (pinfunction "VSSIO_63") (pintype "power_in"))
      (node (ref "U101") (pin "77") (pinfunction "VSSIO_77") (pintype "power_in"))
      (node (ref "U101") (pin "84") (pinfunction "VSSCORE_84") (pintype "power_in"))
      (node (ref "U101") (pin "93") (pinfunction "VSSIO_93") (pintype "power_in"))
      (node (ref "U102") (pin "27") (pinfunction "VSS2_27") (pintype "power_in"))
      (node (ref "U102") (pin "46") (pinfunction "VSS1_46") (pintype "power_in"))
      (node (ref "U103") (pin "12") (pinfunction "VSS1_12") (pintype "power_in"))
      (node (ref "U103") (pin "34") (pinfunction "VSS2_34") (pintype "power_in"))
      (node (ref "X101") (pin "3") (pinfunction "3_3") (pintype "passive"))
    )
    (net (code "109") (name "Net-(U101F-RTCX1)") (class "Default")
      (node (ref "C122") (pin "1") (pinfunction "1_1") (pintype "passive"))
      (node (ref "U101") (pin "34") (pinfunction "RTCX1_34") (pintype "input"))
      (node (ref "X102") (pin "2") (pinfunction "OSC2_2") (pintype "passive"))
    )
    (net (code "110") (name "Net-(U101F-RTCX2)") (class "Default")
      (node (ref "C123") (pin "2") (pinfunction "2_2") (pintype "passive"))
      (node (ref "U101") (pin "36") (pinfunction "RTCX2_36") (pintype "output"))
      (node (ref "X102") (pin "1") (pinfunction "OSC1_1") (pintype "passive"))
    )
    (net (code "111") (name "Net-(U101F-XTAL1)") (class "Default")
      (node (ref "C120") (pin "1") (pinfunction "1_1") (pintype "passive"))
      (node (ref "U101") (pin "44") (pinfunction "XTAL1_44") (pintype "input"))
      (node (ref "X101") (pin "1") (pinfunction "OSC1_1") (pintype "passive"))
    )
    (net (code "112") (name "Net-(U101F-XTAL2)") (class "Default")
      (node (ref "C121") (pin "2") (pinfunction "2_2") (pintype "passive"))
      (node (ref "U101") (pin "46") (pinfunction "XTAL2_46") (pintype "output"))
      (node (ref "X101") (pin "2") (pinfunction "OSC2_2") (pintype "passive"))
    )
    (net (code "113") (name "Net-(U101F-~{RSTOUT})") (class "Default")
      (node (ref "R101") (pin "1") (pinfunction "1_1") (pintype "passive"))
      (node (ref "U101") (pin "29") (pinfunction "~{RSTOUT}_29") (pintype "output"))
    )
    (net (code "114") (name "Net-(U101H-VDDA)") (class "Default")
      (node (ref "C114") (pin "2") (pinfunction "2_2") (pintype "passive"))
      (node (ref "C115") (pin "2") (pinfunction "2_2") (pintype "passive"))
      (node (ref "FB101") (pin "2") (pinfunction "2_2") (pintype "passive"))
      (node (ref "U101") (pin "20") (pinfunction "VDDA_20") (pintype "power_in"))
    )
    (net (code "115") (name "unconnected-(U101A-P0[0]{slash}RD1{slash}TXD3{slash}SDA1-Pad94)") (class "Default")
      (node (ref "U101") (pin "94") (pinfunction "P0[0]/RD1/TXD3/SDA1_94") (pintype "bidirectional"))
    )
    (net (code "116") (name "unconnected-(U101A-P0[1]{slash}TD1{slash}RXD3{slash}SCL1-Pad96)") (class "Default")
      (node (ref "U101") (pin "96") (pinfunction "P0[1]/TD1/RXD3/SCL1_96") (pintype "bidirectional"))
    )
    (net (code "117") (name "unconnected-(U101A-P0[4]{slash}I2SRX_CLK{slash}RD2{slash}CAP2[0]-Pad168)") (class "Default")
      (node (ref "U101") (pin "168") (pinfunction "P0[4]/I2SRX_CLK/RD2/CAP2[0]_168") (pintype "bidirectional"))
    )
    (net (code "118") (name "unconnected-(U101A-P0[5]{slash}I2SRX_WS{slash}TD2{slash}CAP2[1]-Pad166)") (class "Default")
      (node (ref "U101") (pin "166") (pinfunction "P0[5]/I2SRX_WS/TD2/CAP2[1]_166") (pintype "bidirectional"))
    )
    (net (code "119") (name "unconnected-(U101A-P0[6]{slash}I2SRX_SDA{slash}SSEL1{slash}MAT2[0]-Pad164)") (class "Default")
      (node (ref "U101") (pin "164") (pinfunction "P0[6]/I2SRX_SDA/SSEL1/MAT2[0]_164") (pintype "bidirectional"))
    )
    (net (code "120") (name "unconnected-(U101A-P0[7]{slash}I2STX_CLK{slash}SCK1{slash}MAT2[1]-Pad162)") (class "Default")
      (node (ref "U101") (pin "162") (pinfunction "P0[7]/I2STX_CLK/SCK1/MAT2[1]_162") (pintype "bidirectional"))
    )
    (net (code "121") (name "unconnected-(U101A-P0[8]{slash}I2STX_WS{slash}MISO1{slash}MAT2[2]-Pad160)") (class "Default")
      (node (ref "U101") (pin "160") (pinfunction "P0[8]/I2STX_WS/MISO1/MAT2[2]_160") (pintype "bidirectional"))
    )
    (net (code "122") (name "unconnected-(U101A-P0[9]{slash}I2STX_SDA{slash}MOSI1{slash}MAT2[3]-Pad158)") (class "Default")
      (node (ref "U101") (pin "158") (pinfunction "P0[9]/I2STX_SDA/MOSI1/MAT2[3]_158") (pintype "bidirectional"))
    )
    (net (code "123") (name "unconnected-(U101A-P0[10]{slash}TXD2{slash}SDA2{slash}MAT3[0]-Pad98)") (class "Default")
      (node (ref "U101") (pin "98") (pinfunction "P0[10]/TXD2/SDA2/MAT3[0]_98") (pintype "bidirectional"))
    )
    (net (code "124") (name "unconnected-(U101A-P0[11]{slash}RXD2{slash}SCL2{slash}MAT3[1]-Pad100)") (class "Default")
      (node (ref "U101") (pin "100") (pinfunction "P0[11]/RXD2/SCL2/MAT3[1]_100") (pintype "bidirectional"))
    )
    (net (code "125") (name "unconnected-(U101A-P0[12]{slash}~{USB_PPWR}2{slash}MISO1{slash}AD0[6]-Pad41)") (class "Default")
      (node (ref "U101") (pin "41") (pinfunction "P0[12]/~{USB_PPWR}2/MISO1/AD0[6]_41") (pintype "bidirectional"))
    )
    (net (code "126") (name "unconnected-(U101A-P0[13]{slash}USB_UP_LED2{slash}MOSI1{slash}AD0[7]-Pad45)") (class "Default")
      (node (ref "U101") (pin "45") (pinfunction "P0[13]/USB_UP_LED2/MOSI1/AD0[7]_45") (pintype "bidirectional"))
    )
    (net (code "127") (name "unconnected-(U101A-P0[15]{slash}TXD1{slash}SCK0{slash}SCK-Pad128)") (class "Default")
      (node (ref "U101") (pin "128") (pinfunction "P0[15]/TXD1/SCK0/SCK_128") (pintype "bidirectional"))
    )
    (net (code "128") (name "unconnected-(U101A-P0[16]{slash}RXD1{slash}SSEL0{slash}SSEL-Pad130)") (class "Default")
      (node (ref "U101") (pin "130") (pinfunction "P0[16]/RXD1/SSEL0/SSEL_130") (pintype "bidirectional"))
    )
    (net (code "129") (name "unconnected-(U101A-P0[17]{slash}CTS1{slash}MISO0{slash}MISO-Pad126)") (class "Default")
      (node (ref "U101") (pin "126") (pinfunction "P0[17]/CTS1/MISO0/MISO_126") (pintype "bidirectional"))
    )
    (net (code "130") (name "unconnected-(U101A-P0[18]{slash}DCD1{slash}MOSI0{slash}MOSI-Pad124)") (class "Default")
      (node (ref "U101") (pin "124") (pinfunction "P0[18]/DCD1/MOSI0/MOSI_124") (pintype "bidirectional"))
    )
    (net (code "131") (name "unconnected-(U101A-P0[19]{slash}DSR1{slash}MCICLK{slash}SDA1-Pad122)") (class "Default")
      (node (ref "U101") (pin "122") (pinfunction "P0[19]/DSR1/MCICLK/SDA1_122") (pintype "bidirectional"))
    )
    (net (code "132") (name "unconnected-(U101A-P0[20]{slash}DTR1{slash}MCICMD{slash}SCL1-Pad120)") (class "Default")
      (node (ref "U101") (pin "120") (pinfunction "P0[20]/DTR1/MCICMD/SCL1_120") (pintype "bidirectional"))
    )
    (net (code "133") (name "unconnected-(U101A-P0[21]{slash}RI1{slash}MCIPWR{slash}RD1-Pad118)") (class "Default")
      (node (ref "U101") (pin "118") (pinfunction "P0[21]/RI1/MCIPWR/RD1_118") (pintype "bidirectional"))
    )
    (net (code "134") (name "unconnected-(U101A-P0[22]{slash}RTS1{slash}MCIDAT0{slash}TD1-Pad116)") (class "Default")
      (node (ref "U101") (pin "116") (pinfunction "P0[22]/RTS1/MCIDAT0/TD1_116") (pintype "bidirectional"))
    )
    (net (code "135") (name "unconnected-(U101A-P0[23]{slash}AD0[0]{slash}I2SRX_CLK{slash}CAP3[0]-Pad18)") (class "Default")
      (node (ref "U101") (pin "18") (pinfunction "P0[23]/AD0[0]/I2SRX_CLK/CAP3[0]_18") (pintype "bidirectional"))
    )
    (net (code "136") (name "unconnected-(U101A-P0[24]{slash}AD0[1]{slash}I2SRX_WS{slash}CAP3[1]-Pad16)") (class "Default")
      (node (ref "U101") (pin "16") (pinfunction "P0[24]/AD0[1]/I2SRX_WS/CAP3[1]_16") (pintype "bidirectional"))
    )
    (net (code "137") (name "unconnected-(U101A-P0[25]{slash}AD0[2]{slash}I2SRX_SDA{slash}TXD3-Pad14)") (class "Default")
      (node (ref "U101") (pin "14") (pinfunction "P0[25]/AD0[2]/I2SRX_SDA/TXD3_14") (pintype "bidirectional"))
    )
    (net (code "138") (name "unconnected-(U101A-P0[26]{slash}AD0[3]{slash}AOUT{slash}RXD3-Pad12)") (class "Default")
      (node (ref "U101") (pin "12") (pinfunction "P0[26]/AD0[3]/AOUT/RXD3_12") (pintype "bidirectional"))
    )
    (net (code "139") (name "unconnected-(U101A-P0[27]{slash}SDA0-Pad50)") (class "Default")
      (node (ref "U101") (pin "50") (pinfunction "P0[27]/SDA0_50") (pintype "bidirectional"))
    )
    (net (code "140") (name "unconnected-(U101A-P0[28]{slash}SCL0-Pad48)") (class "Default")
      (node (ref "U101") (pin "48") (pinfunction "P0[28]/SCL0_48") (pintype "bidirectional"))
    )
    (net (code "141") (name "unconnected-(U101A-P0[29]{slash}USB_D+1-Pad61)") (class "Default")
      (node (ref "U101") (pin "61") (pinfunction "P0[29]/USB_D+1_61") (pintype "bidirectional"))
    )
    (net (code "142") (name "unconnected-(U101A-P0[30]{slash}USB_D-1-Pad62)") (class "Default")
      (node (ref "U101") (pin "62") (pinfunction "P0[30]/USB_D-1_62") (pintype "bidirectional"))
    )
    (net (code "143") (name "unconnected-(U101A-P0[31]{slash}USB_D+2-Pad51)") (class "Default")
      (node (ref "U101") (pin "51") (pinfunction "P0[31]/USB_D+2_51") (pintype "bidirectional"))
    )
    (net (code "144") (name "unconnected-(U101B-P1[0]{slash}ENET_TXD0-Pad196)") (class "Default")
      (node (ref "U101") (pin "196") (pinfunction "P1[0]/ENET_TXD0_196") (pintype "bidirectional"))
    )
    (net (code "145") (name "unconnected-(U101B-P1[1]{slash}ENET_TXD1-Pad194)") (class "Default")
      (node (ref "U101") (pin "194") (pinfunction "P1[1]/ENET_TXD1_194") (pintype "bidirectional"))
    )
    (net (code "146") (name "unconnected-(U101B-P1[2]{slash}ENET_TXD2{slash}MCICLK{slash}PWM0[1]-Pad185)") (class "Default")
      (node (ref "U101") (pin "185") (pinfunction "P1[2]/ENET_TXD2/MCICLK/PWM0[1]_185") (pintype "bidirectional"))
    )
    (net (code "147") (name "unconnected-(U101B-P1[3]{slash}ENET_TXD3{slash}MCICMD{slash}PWM0[2]-Pad177)") (class "Default")
      (node (ref "U101") (pin "177") (pinfunction "P1[3]/ENET_TXD3/MCICMD/PWM0[2]_177") (pintype "bidirectional"))
    )
    (net (code "148") (name "unconnected-(U101B-P1[4]{slash}ENET_TX_EN-Pad192)") (class "Default")
      (node (ref "U101") (pin "192") (pinfunction "P1[4]/ENET_TX_EN_192") (pintype "bidirectional"))
    )
    (net (code "149") (name "unconnected-(U101B-P1[5]{slash}ENET_TX_ER{slash}MCIPWR{slash}PWM0[3]-Pad156)") (class "Default")
      (node (ref "U101") (pin "156") (pinfunction "P1[5]/ENET_TX_ER/MCIPWR/PWM0[3]_156") (pintype "bidirectional"))
    )
    (net (code "150") (name "unconnected-(U101B-P1[6]{slash}ENET_TX_CLK{slash}MCIDAT0{slash}PWM0[4]-Pad171)") (class "Default")
      (node (ref "U101") (pin "171") (pinfunction "P1[6]/ENET_TX_CLK/MCIDAT0/PWM0[4]_171") (pintype "bidirectional"))
    )
    (net (code "151") (name "unconnected-(U101B-P1[7]{slash}ENET_COL{slash}MCIDAT1{slash}PWM0[5]-Pad153)") (class "Default")
      (node (ref "U101") (pin "153") (pinfunction "P1[7]/ENET_COL/MCIDAT1/PWM0[5]_153") (pintype "bidirectional"))
    )
    (net (code "152") (name "unconnected-(U101B-P1[8]{slash}ENET_CRS_DV{slash}ENET_CRS-Pad190)") (class "Default")
      (node (ref "U101") (pin "190") (pinfunction "P1[8]/ENET_CRS_DV/ENET_CRS_190") (pintype "bidirectional"))
    )
    (net (code "153") (name "unconnected-(U101B-P1[9]{slash}ENET_RXD0-Pad188)") (class "Default")
      (node (ref "U101") (pin "188") (pinfunction "P1[9]/ENET_RXD0_188") (pintype "bidirectional"))
    )
    (net (code "154") (name "unconnected-(U101B-P1[10]{slash}ENET_RXD1-Pad186)") (class "Default")
      (node (ref "U101") (pin "186") (pinfunction "P1[10]/ENET_RXD1_186") (pintype "bidirectional"))
    )
    (net (code "155") (name "unconnected-(U101B-P1[11]{slash}ENET_RXD2{slash}MCIDAT2{slash}PWM0[6]-Pad163)") (class "Default")
      (node (ref "U101") (pin "163") (pinfunction "P1[11]/ENET_RXD2/MCIDAT2/PWM0[6]_163") (pintype "bidirectional"))
    )
    (net (code "156") (name "unconnected-(U101B-P1[12]{slash}ENET_RXD3{slash}MCIDAT3{slash}PCAP0[0]-Pad157)") (class "Default")
      (node (ref "U101") (pin "157") (pinfunction "P1[12]/ENET_RXD3/MCIDAT3/PCAP0[0]_157") (pintype "bidirectional"))
    )
    (net (code "157") (name "unconnected-(U101B-P1[13]{slash}ENET_RX_DV-Pad147)") (class "Default")
      (node (ref "U101") (pin "147") (pinfunction "P1[13]/ENET_RX_DV_147") (pintype "bidirectional"))
    )
    (net (code "158") (name "unconnected-(U101B-P1[14]{slash}ENET_RX_ER-Pad184)") (class "Default")
      (node (ref "U101") (pin "184") (pinfunction "P1[14]/ENET_RX_ER_184") (pintype "bidirectional"))
    )
    (net (code "159") (name "unconnected-(U101B-P1[15]{slash}ENET_REF_CLK{slash}ENET_RX_CLK-Pad182)") (class "Default")
      (node (ref "U101") (pin "182") (pinfunction "P1[15]/ENET_REF_CLK/ENET_RX_CLK_182") (pintype "bidirectional"))
    )
    (net (code "160") (name "unconnected-(U101B-P1[16]{slash}ENET_MDC-Pad180)") (class "Default")
      (node (ref "U101") (pin "180") (pinfunction "P1[16]/ENET_MDC_180") (pintype "bidirectional"))
    )
    (net (code "161") (name "unconnected-(U101B-P1[17]{slash}ENET_MDIO-Pad178)") (class "Default")
      (node (ref "U101") (pin "178") (pinfunction "P1[17]/ENET_MDIO_178") (pintype "bidirectional"))
    )
    (net (code "162") (name "unconnected-(U101B-P1[27]{slash}~{USB_INT}1{slash}~{USB_OVRCR}1{slash}CAP0[1]-Pad88)") (class "Default")
      (node (ref "U101") (pin "88") (pinfunction "P1[27]/~{USB_INT}1/~{USB_OVRCR}1/CAP0[1]_88") (pintype "bidirectional"))
    )
    (net (code "163") (name "unconnected-(U101B-P1[28]{slash}USB_SCL1{slash}PCAP1[0]{slash}MAT0[0]-Pad90)") (class "Default")
      (node (ref "U101") (pin "90") (pinfunction "P1[28]/USB_SCL1/PCAP1[0]/MAT0[0]_90") (pintype "bidirectional"))
    )
    (net (code "164") (name "unconnected-(U101B-P1[29]{slash}USB_SDA1{slash}PCAP1[1]{slash}MAT0[1]-Pad92)") (class "Default")
      (node (ref "U101") (pin "92") (pinfunction "P1[29]/USB_SDA1/PCAP1[1]/MAT0[1]_92") (pintype "bidirectional"))
    )
    (net (code "165") (name "unconnected-(U101B-P1[30]{slash}USB_PWRD2{slash}VBUS{slash}AD0[4]-Pad42)") (class "Default")
      (node (ref "U101") (pin "42") (pinfunction "P1[30]/USB_PWRD2/VBUS/AD0[4]_42") (pintype "bidirectional"))
    )
    (net (code "166") (name "unconnected-(U101B-P1[31]{slash}~{USB_OVRCR}2{slash}SCK1{slash}AD0[5]-Pad40)") (class "Default")
      (node (ref "U101") (pin "40") (pinfunction "P1[31]/~{USB_OVRCR}2/SCK1/AD0[5]_40") (pintype "bidirectional"))
    )
    (net (code "167") (name "unconnected-(U101C-P2[0]{slash}PWM1[1]{slash}TXD1{slash}TRACECLK-Pad154)") (class "Default")
      (node (ref "U101") (pin "154") (pinfunction "P2[0]/PWM1[1]/TXD1/TRACECLK_154") (pintype "bidirectional"))
    )
    (net (code "168") (name "unconnected-(U101C-P2[5]{slash}PWM1[6]{slash}DTR1{slash}TRACEPKT0-Pad140)") (class "Default")
      (node (ref "U101") (pin "140") (pinfunction "P2[5]/PWM1[6]/DTR1/TRACEPKT0_140") (pintype "bidirectional"))
    )
    (net (code "169") (name "unconnected-(U101C-P2[14]{slash}~{CS}2{slash}CAP2[0]{slash}SDA1-Pad91)") (class "Default")
      (node (ref "U101") (pin "91") (pinfunction "P2[14]/~{CS}2/CAP2[0]/SDA1_91") (pintype "bidirectional"))
    )
    (net (code "170") (name "unconnected-(U101C-P2[16]{slash}~{CAS}-Pad87)") (class "Default")
      (node (ref "U101") (pin "87") (pinfunction "P2[16]/~{CAS}_87") (pintype "bidirectional"))
    )
    (net (code "171") (name "unconnected-(U101C-P2[22]{slash}~{DYCS}2{slash}CAP3[0]{slash}SCK0-Pad85)") (class "Default")
      (node (ref "U101") (pin "85") (pinfunction "P2[22]/~{DYCS}2/CAP3[0]/SCK0_85") (pintype "bidirectional"))
    )
    (net (code "172") (name "unconnected-(U101C-P2[24]{slash}CKEOUT0-Pad53)") (class "Default")
      (node (ref "U101") (pin "53") (pinfunction "P2[24]/CKEOUT0_53") (pintype "bidirectional"))
    )
    (net (code "173") (name "unconnected-(U101C-P2[27]{slash}CKEOUT3{slash}MAT3[1]{slash}MOSI0-Pad47)") (class "Default")
      (node (ref "U101") (pin "47") (pinfunction "P2[27]/CKEOUT3/MAT3[1]/MOSI0_47") (pintype "bidirectional"))
    )
    (net (code "174") (name "unconnected-(U101C-P2[28]{slash}DQMOUT0-Pad49)") (class "Default")
      (node (ref "U101") (pin "49") (pinfunction "P2[28]/DQMOUT0_49") (pintype "bidirectional"))
    )
    (net (code "175") (name "unconnected-(U101C-P2[29]{slash}DQMOUT1-Pad43)") (class "Default")
      (node (ref "U101") (pin "43") (pinfunction "P2[29]/DQMOUT1_43") (pintype "bidirectional"))
    )
    (net (code "176") (name "unconnected-(U101C-P2[30]{slash}DQMOUT2{slash}MAT3[2]{slash}SDA2-Pad31)") (class "Default")
      (node (ref "U101") (pin "31") (pinfunction "P2[30]/DQMOUT2/MAT3[2]/SDA2_31") (pintype "bidirectional"))
    )
    (net (code "177") (name "unconnected-(U101C-P2[31]{slash}DQMOUT3{slash}MAT3[3]{slash}SCL2-Pad39)") (class "Default")
      (node (ref "U101") (pin "39") (pinfunction "P2[31]/DQMOUT3/MAT3[3]/SCL2_39") (pintype "bidirectional"))
    )
    (net (code "178") (name "unconnected-(U101D-P3[16]{slash}D16{slash}PWM0[1]{slash}TXD1-Pad137)") (class "Default")
      (node (ref "U101") (pin "137") (pinfunction "P3[16]/D16/PWM0[1]/TXD1_137") (pintype "bidirectional"))
    )
    (net (code "179") (name "unconnected-(U101D-P3[17]{slash}D17{slash}PWM0[2]{slash}RXD1-Pad143)") (class "Default")
      (node (ref "U101") (pin "143") (pinfunction "P3[17]/D17/PWM0[2]/RXD1_143") (pintype "bidirectional"))
    )
    (net (code "180") (name "unconnected-(U101D-P3[18]{slash}D18{slash}PWM0[3]{slash}CTS1-Pad151)") (class "Default")
      (node (ref "U101") (pin "151") (pinfunction "P3[18]/D18/PWM0[3]/CTS1_151") (pintype "bidirectional"))
    )
    (net (code "181") (name "unconnected-(U101D-P3[19]{slash}D19{slash}PWM0[4]{slash}DCD1-Pad161)") (class "Default")
      (node (ref "U101") (pin "161") (pinfunction "P3[19]/D19/PWM0[4]/DCD1_161") (pintype "bidirectional"))
    )
    (net (code "182") (name "unconnected-(U101D-P3[20]{slash}D20{slash}PWM0[5]{slash}DSR1-Pad167)") (class "Default")
      (node (ref "U101") (pin "167") (pinfunction "P3[20]/D20/PWM0[5]/DSR1_167") (pintype "bidirectional"))
    )
    (net (code "183") (name "unconnected-(U101D-P3[21]{slash}D21{slash}PWM0[6]{slash}DTR1-Pad175)") (class "Default")
      (node (ref "U101") (pin "175") (pinfunction "P3[21]/D21/PWM0[6]/DTR1_175") (pintype "bidirectional"))
    )
    (net (code "184") (name "unconnected-(U101D-P3[22]{slash}D22{slash}PCAP0[0]{slash}RI1-Pad195)") (class "Default")
      (node (ref "U101") (pin "195") (pinfunction "P3[22]/D22/PCAP0[0]/RI1_195") (pintype "bidirectional"))
    )
    (net (code "185") (name "unconnected-(U101D-P3[27]{slash}D27{slash}CAP1[0]{slash}PWM1[4]-Pad203)") (class "Default")
      (node (ref "U101") (pin "203") (pinfunction "P3[27]/D27/CAP1[0]/PWM1[4]_203") (pintype "bidirectional"))
    )
    (net (code "186") (name "unconnected-(U101D-P3[28]{slash}D28{slash}CAP1[1]{slash}PWM1[5]-Pad5)") (class "Default")
      (node (ref "U101") (pin "5") (pinfunction "P3[28]/D28/CAP1[1]/PWM1[5]_5") (pintype "bidirectional"))
    )
    (net (code "187") (name "unconnected-(U101D-P3[29]{slash}D29{slash}MAT1[0]{slash}PWM1[6]-Pad11)") (class "Default")
      (node (ref "U101") (pin "11") (pinfunction "P3[29]/D29/MAT1[0]/PWM1[6]_11") (pintype "bidirectional"))
    )
    (net (code "188") (name "unconnected-(U101D-P3[30]{slash}D30{slash}MAT1[1]{slash}RTS1-Pad19)") (class "Default")
      (node (ref "U101") (pin "19") (pinfunction "P3[30]/D30/MAT1[1]/RTS1_19") (pintype "bidirectional"))
    )
    (net (code "189") (name "unconnected-(U101D-P3[31]{slash}D31{slash}MAT1[2]-Pad25)") (class "Default")
      (node (ref "U101") (pin "25") (pinfunction "P3[31]/D31/MAT1[2]_25") (pintype "bidirectional"))
    )
    (net (code "190") (name "unconnected-(U101E-P4[0]{slash}A0-Pad75)") (class "Default")
      (node (ref "U101") (pin "75") (pinfunction "P4[0]/A0_75") (pintype "bidirectional+no_connect"))
    )
    (net (code "191") (name "unconnected-(U101E-P4[28]{slash}BLS2{slash}MAT2[0]{slash}TXD3-Pad170)") (class "Default")
      (node (ref "U101") (pin "170") (pinfunction "P4[28]/BLS2/MAT2[0]/TXD3_170") (pintype "bidirectional"))
    )
    (net (code "192") (name "unconnected-(U101E-P4[29]{slash}BLS3{slash}MAT2[1]{slash}RXD3-Pad176)") (class "Default")
      (node (ref "U101") (pin "176") (pinfunction "P4[29]/BLS3/MAT2[1]/RXD3_176") (pintype "bidirectional"))
    )
    (net (code "193") (name "unconnected-(U101F-ALARM-Pad37)") (class "Default")
      (node (ref "U101") (pin "37") (pinfunction "ALARM_37") (pintype "output+no_connect"))
    )
    (net (code "194") (name "unconnected-(U101F-USB_D-2-Pad52)") (class "Default")
      (node (ref "U101") (pin "52") (pinfunction "USB_D-2_52") (pintype "bidirectional+no_connect"))
    )
    (net (code "195") (name "unconnected-(U101I-NC-Pad30)") (class "Default")
      (node (ref "U101") (pin "30") (pinfunction "NC_30") (pintype "passive+no_connect"))
    )
    (net (code "196") (name "unconnected-(U101I-NC-Pad117)") (class "Default")
      (node (ref "U101") (pin "117") (pinfunction "NC_117") (pintype "passive+no_connect"))
    )
    (net (code "197") (name "unconnected-(U101I-NC-Pad141)") (class "Default")
      (node (ref "U101") (pin "141") (pinfunction "NC_141") (pintype "passive+no_connect"))
    )
    (net (code "198") (name "unconnected-(U102-DNU-Pad13)") (class "Default")
      (node (ref "U102") (pin "13") (pinfunction "DNU_13") (pintype "passive+no_connect"))
    )
    (net (code "199") (name "unconnected-(U102-NC-Pad10)") (class "Default")
      (node (ref "U102") (pin "10") (pinfunction "NC_10") (pintype "passive+no_connect"))
    )
  )
)
